# Overview.net
KiCad netlist of a schematic drawn in Altium Designer
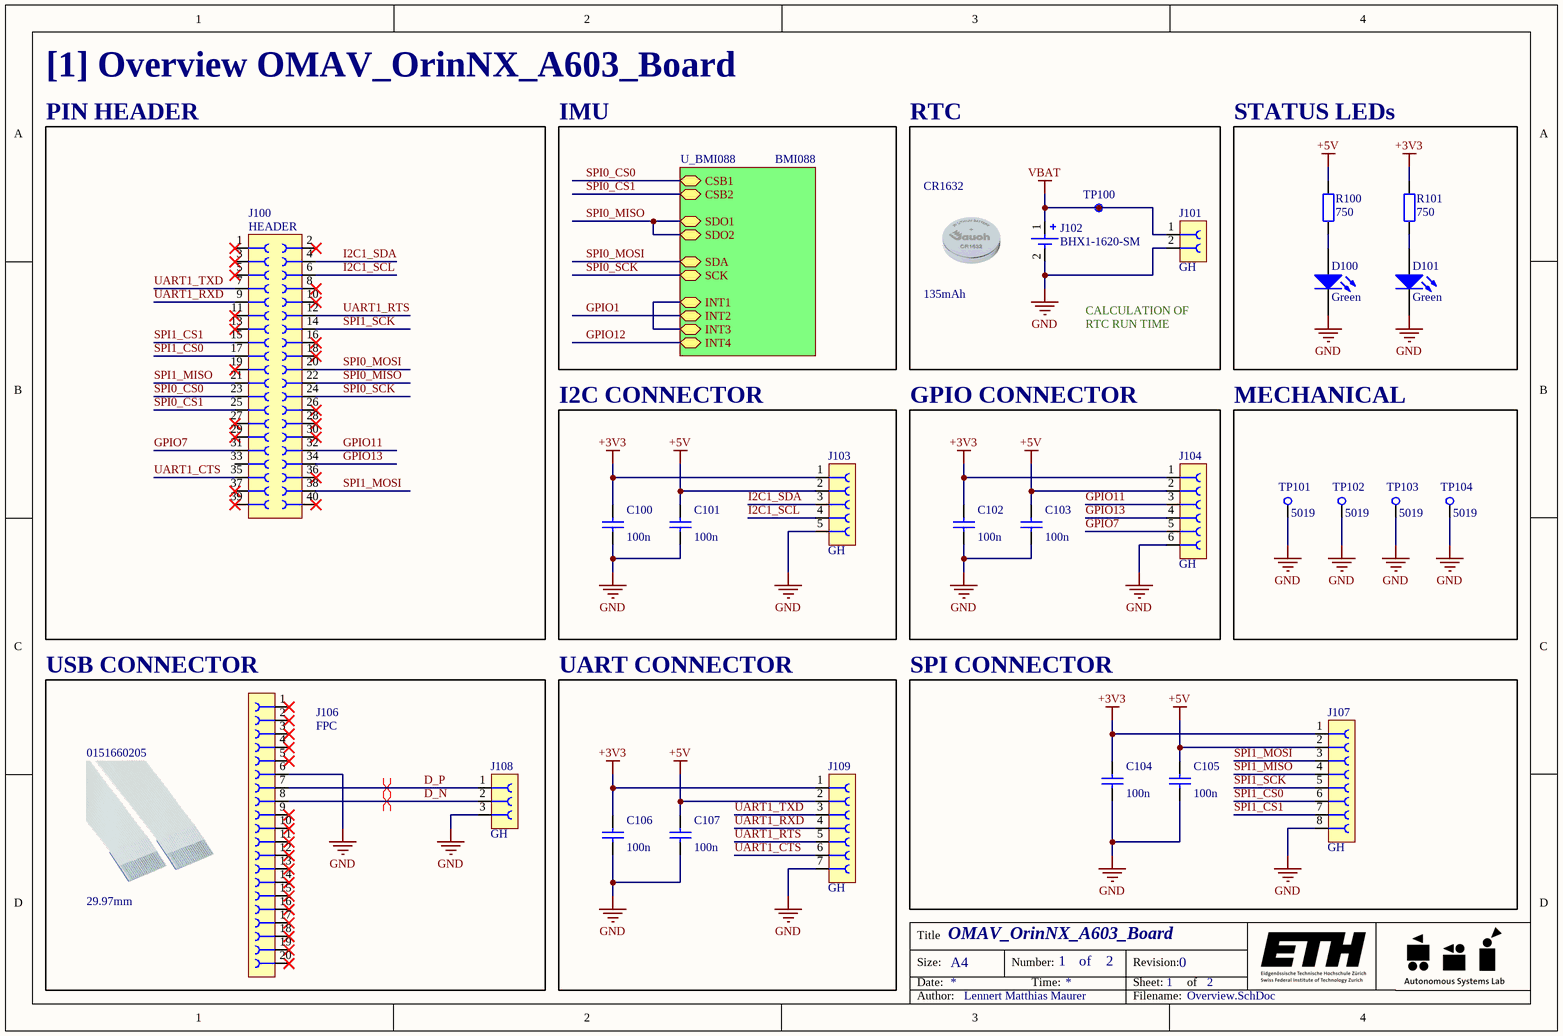
[diagram p0: Overview.SchDoc]

(export (version "E")
  (design (tool "Eeschema 10.0.6"))
  (components
    (comp (ref "C100")
      (value "100n")
      (footprint "SMD_CAPC2012X12N")
      (description "CERCAP 100n 100V 10% X7R 0603")
      (fields
        (field (name "MANUFACTURER") "Murata")
        (field (name "MANUFACTURER PART NUMBER") "GRM188R72A104KA35D")
      )
      (libsource (lib "ETHZ Vault") (part "Cap"))
    )
    (comp (ref "C101")
      (value "100n")
      (footprint "SMD_CAPC2012X12N")
      (description "CERCAP 100n 100V 10% X7R 0603")
      (fields
        (field (name "MANUFACTURER") "Murata")
        (field (name "MANUFACTURER PART NUMBER") "GRM188R72A104KA35D")
      )
      (libsource (lib "ETHZ Vault") (part "Cap"))
    )
    (comp (ref "C102")
      (value "100n")
      (footprint "SMD_CAPC2012X12N")
      (description "CERCAP 100n 100V 10% X7R 0603")
      (fields
        (field (name "MANUFACTURER") "Murata")
        (field (name "MANUFACTURER PART NUMBER") "GRM188R72A104KA35D")
      )
      (libsource (lib "ETHZ Vault") (part "Cap"))
    )
    (comp (ref "C103")
      (value "100n")
      (footprint "SMD_CAPC2012X12N")
      (description "CERCAP 100n 100V 10% X7R 0603")
      (fields
        (field (name "MANUFACTURER") "Murata")
        (field (name "MANUFACTURER PART NUMBER") "GRM188R72A104KA35D")
      )
      (libsource (lib "ETHZ Vault") (part "Cap"))
    )
    (comp (ref "C104")
      (value "100n")
      (footprint "SMD_CAPC2012X12N")
      (description "CERCAP 100n 100V 10% X7R 0603")
      (fields
        (field (name "MANUFACTURER") "Murata")
        (field (name "MANUFACTURER PART NUMBER") "GRM188R72A104KA35D")
      )
      (libsource (lib "ETHZ Vault") (part "Cap"))
    )
    (comp (ref "C105")
      (value "100n")
      (footprint "SMD_CAPC2012X12N")
      (description "CERCAP 100n 100V 10% X7R 0603")
      (fields
        (field (name "MANUFACTURER") "Murata")
        (field (name "MANUFACTURER PART NUMBER") "GRM188R72A104KA35D")
      )
      (libsource (lib "ETHZ Vault") (part "Cap"))
    )
    (comp (ref "C106")
      (value "100n")
      (footprint "SMD_CAPC2012X12N")
      (description "CERCAP 100n 100V 10% X7R 0603")
      (fields
        (field (name "MANUFACTURER") "Murata")
        (field (name "MANUFACTURER PART NUMBER") "GRM188R72A104KA35D")
      )
      (libsource (lib "ETHZ Vault") (part "Cap"))
    )
    (comp (ref "C107")
      (value "100n")
      (footprint "SMD_CAPC2012X12N")
      (description "CERCAP 100n 100V 10% X7R 0603")
      (fields
        (field (name "MANUFACTURER") "Murata")
        (field (name "MANUFACTURER PART NUMBER") "GRM188R72A104KA35D")
      )
      (libsource (lib "ETHZ Vault") (part "Cap"))
    )
    (comp (ref "D100")
      (value "Green")
      (footprint "SMD_LED_0402")
      (description "LED GREEN 2mA  1.9V 1x 0.5mm")
      (fields
        (field (name "MANUFACTURER") "Kingbright USA")
        (field (name "MANUFACTURER PART NUMBER") "APHHS1005LCGCK")
      )
      (libsource (lib "ETHZ Vault") (part "Diode LED"))
    )
    (comp (ref "D101")
      (value "Green")
      (footprint "SMD_LED_0402")
      (description "LED GREEN 2mA  1.9V 1x 0.5mm")
      (fields
        (field (name "MANUFACTURER") "Kingbright USA")
        (field (name "MANUFACTURER PART NUMBER") "APHHS1005LCGCK")
      )
      (libsource (lib "ETHZ Vault") (part "Diode LED"))
    )
    (comp (ref "J100")
      (value "HEADER")
      (footprint "NPTC202KFMS-RC")
      (description "RECT-CONN Female 40-Poles 2.54mm Vertical SMD 12.55x51.3mm")
      (fields
        (field (name "MANUFACTURER") "Sullins Connector Solutions")
        (field (name "MANUFACTURER PART NUMBER") "NPTC202KFMS-RC")
      )
      (libsource (lib "ETHZ Vault") (part "CON 20x2 Female"))
    )
    (comp (ref "J101")
      (value "GH")
      (footprint "SMD_CONN_JST_GH_FEMALE _2-POLES_1.25mm_VERTICAL")
      (description "CONN Female GH 2-Poles 1.25mm Vertical SMD 5.75x4.05mm")
      (fields
        (field (name "MANUFACTURER") "JST Sales America Inc.")
        (field (name "MANUFACTURER PART NUMBER") "BM02B-GHS-TBT(LF)(SN)(N)")
      )
      (libsource (lib "ETHZ Vault") (part "CON 2x1 Female"))
    )
    (comp (ref "J102")
      (value "BHX1-1620-SM")
      (footprint "BHX1-1620-SM")
      (description "EMECH SINGLE COIN BATTERY RETAINER SMD 16x3.55mm")
      (fields (field (name "MANUFACTURER") "MPD (Memory Protection Devices)"))
      (libsource (lib "ETHZ Vault") (part "Battery Holder"))
    )
    (comp (ref "J103")
      (value "GH")
      (footprint "SMD_CONN_JST_GH_FEMALE _5-POLES_1.25mm_VERTICAL")
      (description "CONN Female GH 5-Poles 1.25mm Vertical SMD 9.50x4.05mm")
      (fields
        (field (name "MANUFACTURER") "JST Sales America Inc.")
        (field (name "MANUFACTURER PART NUMBER") "BM05B-GHS-TBT(LF)(SN)(N)")
      )
      (libsource (lib "ETHZ Vault") (part "CON 5x1 Female"))
    )
    (comp (ref "J104")
      (value "GH")
      (footprint "SMD_CONN_JST_GH_FEMALE _6-POLES_1.25mm_VERTICAL")
      (description "CONN Female GH 6-Poles 1.25mm Vertical SMD 10.75x4.05mm")
      (fields
        (field (name "MANUFACTURER") "JST Sales America Inc.")
        (field (name "MANUFACTURER PART NUMBER") "BM06B-GHS-TBT(LF)(SN)(N)")
      )
      (libsource (lib "ETHZ Vault") (part "CON 6x1 Female"))
    )
    (comp (ref "J106")
      (value "FPC")
      (footprint "5034802000")
      (description "FPC TOP/BOTTOM 20POS 0.5mm Horizontal SMD")
      (fields (field (name "MANUFACTURER") "Molex") (field (name "MANUFACTURER PART NUMBER") "5034802000"))
      (libsource (lib "ETHZ Vault") (part "CON 20x1 Female"))
    )
    (comp (ref "J107")
      (value "GH")
      (footprint "SMD_CONN_JST_GH_FEMALE _8-POLES_1.25mm_VERTICAL")
      (description "CONN Female GH 8-Poles 1.25mm Vertical SMD 13.25x4.05mm")
      (fields
        (field (name "MANUFACTURER") "JST Sales America Inc.")
        (field (name "MANUFACTURER PART NUMBER") "455-1584-1-ND")
      )
      (libsource (lib "ETHZ Vault") (part "CON 8x1 Female"))
    )
    (comp (ref "J108")
      (value "GH")
      (footprint "SMD_CONN_JST_GH_FEMALE _3-POLES_1.25mm_VERTICAL")
      (description "CONN Female GH 3-Poles 1.25mm Vertical SMD 7.00x4.05mm")
      (fields
        (field (name "MANUFACTURER") "JST Sales America Inc.")
        (field (name "MANUFACTURER PART NUMBER") "SM03B-GHS-TB(LF)(SN)")
      )
      (libsource (lib "ETHZ Vault") (part "CON 3x1 Female"))
    )
    (comp (ref "J109")
      (value "GH")
      (footprint "SMD_CONN_JST_GH_FEMALE _7-POLES_1.25mm_VERTICAL")
      (description "CONN Female GH 7-Poles 1.25mm Vertical SMD 12.00x4.05mm")
      (fields
        (field (name "MANUFACTURER") "JST Sales America Inc.")
        (field (name "MANUFACTURER PART NUMBER") "BM07B-GHS-TBT(LF)(SN)(N)")
      )
      (libsource (lib "ETHZ Vault") (part "CON 7x1 Female"))
    )
    (comp (ref "MEC100")
      (value "CR1632")
      (description "EMECH SINGLE 3V LITHIUM BATTERY 16mm")
      (fields (field (name "MANUFACTURER") "Jauch Quartz") (field (name "ALTIUM_VALUE") "135mAh"))
      (libsource (lib "ETHZ Vault") (part "CR1632"))
    )
    (comp (ref "MEC101")
      (value "0151660205")
      (description "EMECH SINGLE FFC CABLE 20-Pin 0.5mm 29.97mm")
      (fields (field (name "MANUFACTURER") "Molex") (field (name "ALTIUM_VALUE") "29.97mm"))
      (libsource (lib "ETHZ Vault") (part "0151660205"))
    )
    (comp (ref "R100")
      (value "750")
      (footprint "SMD_RESC1005X04N")
      (description "RES 750 100mW 1% 0402")
      (fields
        (field (name "MANUFACTURER") "Panasonic Electronic Components")
        (field (name "MANUFACTURER PART NUMBER") "ERJ-2RKF7500X")
      )
      (libsource (lib "ETHZ Vault") (part "Res"))
    )
    (comp (ref "R101")
      (value "750")
      (footprint "SMD_RESC1005X04N")
      (description "RES 750 100mW 1% 0402")
      (fields
        (field (name "MANUFACTURER") "Panasonic Electronic Components")
        (field (name "MANUFACTURER PART NUMBER") "ERJ-2RKF7500X")
      )
      (libsource (lib "ETHZ Vault") (part "Res"))
    )
    (comp (ref "TP100")
      (value "Test Point Small")
      (footprint "SMD_PAD_0.5mm")
      (description "TP TESTPOINT MULTIPLE_SIZE")
      (libsource (lib "ETHZ Vault") (part "Test Point Small"))
    )
    (comp (ref "TP101")
      (value "5019")
      (footprint "KEYSTONE_5019")
      (description "TP SMD 3.81x 2.03mm")
      (fields (field (name "MANUFACTURER") "Keystone Electronics"))
      (libsource (lib "ETHZ Vault") (part "Test Point"))
    )
    (comp (ref "TP102")
      (value "5019")
      (footprint "KEYSTONE_5019")
      (description "TP SMD 3.81x 2.03mm")
      (fields (field (name "MANUFACTURER") "Keystone Electronics"))
      (libsource (lib "ETHZ Vault") (part "Test Point"))
    )
    (comp (ref "TP103")
      (value "5019")
      (footprint "KEYSTONE_5019")
      (description "TP SMD 3.81x 2.03mm")
      (fields (field (name "MANUFACTURER") "Keystone Electronics"))
      (libsource (lib "ETHZ Vault") (part "Test Point"))
    )
    (comp (ref "TP104")
      (value "5019")
      (footprint "KEYSTONE_5019")
      (description "TP SMD 3.81x 2.03mm")
      (fields (field (name "MANUFACTURER") "Keystone Electronics"))
      (libsource (lib "ETHZ Vault") (part "Test Point"))
    )
  )
  (nets
    (net (code "1") (name "+3V3") (class "Default")
      (node (ref "C100") (pin "2") (pinfunction "2_2") (pintype "passive"))
      (node (ref "C102") (pin "2") (pinfunction "2_2") (pintype "passive"))
      (node (ref "C104") (pin "2") (pinfunction "2_2") (pintype "passive"))
      (node (ref "C106") (pin "2") (pinfunction "2_2") (pintype "passive"))
      (node (ref "J103") (pin "1") (pinfunction "1_1") (pintype "passive"))
      (node (ref "J104") (pin "1") (pinfunction "1_1") (pintype "passive"))
      (node (ref "J107") (pin "1") (pinfunction "1_1") (pintype "passive"))
      (node (ref "J109") (pin "1") (pinfunction "1_1") (pintype "passive"))
      (node (ref "R101") (pin "2") (pinfunction "2_2") (pintype "passive"))
    )
    (net (code "2") (name "+5V") (class "Default")
      (node (ref "C101") (pin "2") (pinfunction "2_2") (pintype "passive"))
      (node (ref "C103") (pin "2") (pinfunction "2_2") (pintype "passive"))
      (node (ref "C105") (pin "2") (pinfunction "2_2") (pintype "passive"))
      (node (ref "C107") (pin "2") (pinfunction "2_2") (pintype "passive"))
      (node (ref "J103") (pin "2") (pinfunction "2_2") (pintype "passive"))
      (node (ref "J104") (pin "2") (pinfunction "2_2") (pintype "passive"))
      (node (ref "J107") (pin "2") (pinfunction "2_2") (pintype "passive"))
      (node (ref "J109") (pin "2") (pinfunction "2_2") (pintype "passive"))
      (node (ref "R100") (pin "2") (pinfunction "2_2") (pintype "passive"))
    )
    (net (code "3") (name "/D_N") (class "Default")
      (node (ref "J106") (pin "8") (pinfunction "8_8") (pintype "passive"))
      (node (ref "J108") (pin "2") (pinfunction "2_2") (pintype "passive"))
    )
    (net (code "4") (name "/D_P") (class "Default")
      (node (ref "J106") (pin "7") (pinfunction "7_7") (pintype "passive"))
      (node (ref "J108") (pin "1") (pinfunction "1_1") (pintype "passive"))
    )
    (net (code "6") (name "/GPIO7") (class "Default")
      (node (ref "J100") (pin "31") (pinfunction "31_31") (pintype "passive"))
      (node (ref "J104") (pin "5") (pinfunction "5_5") (pintype "passive"))
    )
    (net (code "7") (name "/GPIO11") (class "Default")
      (node (ref "J100") (pin "32") (pinfunction "32_32") (pintype "passive"))
      (node (ref "J104") (pin "3") (pinfunction "3_3") (pintype "passive"))
    )
    (net (code "9") (name "/GPIO13") (class "Default")
      (node (ref "J100") (pin "34") (pinfunction "34_34") (pintype "passive"))
      (node (ref "J104") (pin "4") (pinfunction "4_4") (pintype "passive"))
    )
    (net (code "10") (name "/I2C1_SCL") (class "Default")
      (node (ref "J100") (pin "6") (pinfunction "6_6") (pintype "passive"))
      (node (ref "J103") (pin "4") (pinfunction "4_4") (pintype "passive"))
    )
    (net (code "11") (name "/I2C1_SDA") (class "Default")
      (node (ref "J100") (pin "4") (pinfunction "4_4") (pintype "passive"))
      (node (ref "J103") (pin "3") (pinfunction "3_3") (pintype "passive"))
    )
    (net (code "13") (name "/SPI0_CS0") (class "Default")
      (node (ref "J100") (pin "23") (pinfunction "23_23") (pintype "passive"))
    )
    (net (code "14") (name "/SPI0_CS1") (class "Default")
      (node (ref "J100") (pin "25") (pinfunction "25_25") (pintype "passive"))
    )
    (net (code "15") (name "/SPI0_MISO") (class "Default")
      (node (ref "J100") (pin "22") (pinfunction "22_22") (pintype "passive"))
    )
    (net (code "16") (name "/SPI0_MOSI") (class "Default")
      (node (ref "J100") (pin "20") (pinfunction "20_20") (pintype "passive"))
    )
    (net (code "17") (name "/SPI0_SCK") (class "Default")
      (node (ref "J100") (pin "24") (pinfunction "24_24") (pintype "passive"))
    )
    (net (code "18") (name "/SPI1_CS0") (class "Default")
      (node (ref "J100") (pin "17") (pinfunction "17_17") (pintype "passive"))
      (node (ref "J107") (pin "6") (pinfunction "6_6") (pintype "passive"))
    )
    (net (code "19") (name "/SPI1_CS1") (class "Default")
      (node (ref "J100") (pin "15") (pinfunction "15_15") (pintype "passive"))
      (node (ref "J107") (pin "7") (pinfunction "7_7") (pintype "passive"))
    )
    (net (code "20") (name "/SPI1_MISO") (class "Default")
      (node (ref "J100") (pin "21") (pinfunction "21_21") (pintype "passive"))
      (node (ref "J107") (pin "4") (pinfunction "4_4") (pintype "passive"))
    )
    (net (code "21") (name "/SPI1_MOSI") (class "Default")
      (node (ref "J100") (pin "38") (pinfunction "38_38") (pintype "passive"))
      (node (ref "J107") (pin "3") (pinfunction "3_3") (pintype "passive"))
    )
    (net (code "22") (name "/SPI1_SCK") (class "Default")
      (node (ref "J100") (pin "14") (pinfunction "14_14") (pintype "passive"))
      (node (ref "J107") (pin "5") (pinfunction "5_5") (pintype "passive"))
    )
    (net (code "23") (name "/UART1_CTS") (class "Default")
      (node (ref "J100") (pin "35") (pinfunction "35_35") (pintype "passive"))
      (node (ref "J109") (pin "6") (pinfunction "6_6") (pintype "passive"))
    )
    (net (code "24") (name "/UART1_RTS") (class "Default")
      (node (ref "J100") (pin "12") (pinfunction "12_12") (pintype "passive"))
      (node (ref "J109") (pin "5") (pinfunction "5_5") (pintype "passive"))
    )
    (net (code "25") (name "/UART1_RXD") (class "Default")
      (node (ref "J100") (pin "9") (pinfunction "9_9") (pintype "passive"))
      (node (ref "J109") (pin "4") (pinfunction "4_4") (pintype "passive"))
    )
    (net (code "26") (name "/UART1_TXD") (class "Default")
      (node (ref "J100") (pin "7") (pinfunction "7_7") (pintype "passive"))
      (node (ref "J109") (pin "3") (pinfunction "3_3") (pintype "passive"))
    )
    (net (code "27") (name "GND") (class "Default")
      (node (ref "C100") (pin "1") (pinfunction "1_1") (pintype "passive"))
      (node (ref "C101") (pin "1") (pinfunction "1_1") (pintype "passive"))
      (node (ref "C102") (pin "1") (pinfunction "1_1") (pintype "passive"))
      (node (ref "C103") (pin "1") (pinfunction "1_1") (pintype "passive"))
      (node (ref "C104") (pin "1") (pinfunction "1_1") (pintype "passive"))
      (node (ref "C105") (pin "1") (pinfunction "1_1") (pintype "passive"))
      (node (ref "C106") (pin "1") (pinfunction "1_1") (pintype "passive"))
      (node (ref "C107") (pin "1") (pinfunction "1_1") (pintype "passive"))
      (node (ref "D100") (pin "1") (pinfunction "K_1") (pintype "passive"))
      (node (ref "D101") (pin "1") (pinfunction "K_1") (pintype "passive"))
      (node (ref "J101") (pin "2") (pinfunction "2_2") (pintype "passive"))
      (node (ref "J102") (pin "2") (pinfunction "-_2") (pintype "passive"))
      (node (ref "J103") (pin "5") (pinfunction "5_5") (pintype "passive"))
      (node (ref "J104") (pin "6") (pinfunction "6_6") (pintype "passive"))
      (node (ref "J106") (pin "6") (pinfunction "6_6") (pintype "passive"))
      (node (ref "J107") (pin "8") (pinfunction "8_8") (pintype "passive"))
      (node (ref "J108") (pin "3") (pinfunction "3_3") (pintype "passive"))
      (node (ref "J109") (pin "7") (pinfunction "7_7") (pintype "passive"))
      (node (ref "TP101") (pin "1") (pinfunction "1_1") (pintype "passive"))
      (node (ref "TP102") (pin "1") (pinfunction "1_1") (pintype "passive"))
      (node (ref "TP103") (pin "1") (pinfunction "1_1") (pintype "passive"))
      (node (ref "TP104") (pin "1") (pinfunction "1_1") (pintype "passive"))
    )
    (net (code "28") (name "Net-(D100-A)") (class "Default")
      (node (ref "D100") (pin "2") (pinfunction "A_2") (pintype "passive"))
      (node (ref "R100") (pin "1") (pinfunction "1_1") (pintype "passive"))
    )
    (net (code "29") (name "Net-(D101-A)") (class "Default")
      (node (ref "D101") (pin "2") (pinfunction "A_2") (pintype "passive"))
      (node (ref "R101") (pin "1") (pinfunction "1_1") (pintype "passive"))
    )
    (net (code "30") (name "VBAT") (class "Default")
      (node (ref "J101") (pin "1") (pinfunction "1_1") (pintype "passive"))
      (node (ref "J102") (pin "1") (pinfunction "+_1") (pintype "passive"))
      (node (ref "TP100") (pin "1") (pinfunction "1_1") (pintype "passive"))
    )
    (net (code "31") (name "unconnected-(J100-Pad1)") (class "Default")
      (node (ref "J100") (pin "1") (pinfunction "1_1") (pintype "passive+no_connect"))
    )
    (net (code "32") (name "unconnected-(J100-Pad2)") (class "Default")
      (node (ref "J100") (pin "2") (pinfunction "2_2") (pintype "passive+no_connect"))
    )
    (net (code "33") (name "unconnected-(J100-Pad3)") (class "Default")
      (node (ref "J100") (pin "3") (pinfunction "3_3") (pintype "passive+no_connect"))
    )
    (net (code "34") (name "unconnected-(J100-Pad5)") (class "Default")
      (node (ref "J100") (pin "5") (pinfunction "5_5") (pintype "passive+no_connect"))
    )
    (net (code "35") (name "unconnected-(J100-Pad8)") (class "Default")
      (node (ref "J100") (pin "8") (pinfunction "8_8") (pintype "passive+no_connect"))
    )
    (net (code "36") (name "unconnected-(J100-Pad10)") (class "Default")
      (node (ref "J100") (pin "10") (pinfunction "10_10") (pintype "passive+no_connect"))
    )
    (net (code "37") (name "unconnected-(J100-Pad11)") (class "Default")
      (node (ref "J100") (pin "11") (pinfunction "11_11") (pintype "passive+no_connect"))
    )
    (net (code "38") (name "unconnected-(J100-Pad13)") (class "Default")
      (node (ref "J100") (pin "13") (pinfunction "13_13") (pintype "passive+no_connect"))
    )
    (net (code "39") (name "unconnected-(J100-Pad16)") (class "Default")
      (node (ref "J100") (pin "16") (pinfunction "16_16") (pintype "passive+no_connect"))
    )
    (net (code "40") (name "unconnected-(J100-Pad18)") (class "Default")
      (node (ref "J100") (pin "18") (pinfunction "18_18") (pintype "passive+no_connect"))
    )
    (net (code "41") (name "unconnected-(J100-Pad19)") (class "Default")
      (node (ref "J100") (pin "19") (pinfunction "19_19") (pintype "passive+no_connect"))
    )
    (net (code "42") (name "unconnected-(J100-Pad26)") (class "Default")
      (node (ref "J100") (pin "26") (pinfunction "26_26") (pintype "passive+no_connect"))
    )
    (net (code "43") (name "unconnected-(J100-Pad27)") (class "Default")
      (node (ref "J100") (pin "27") (pinfunction "27_27") (pintype "passive+no_connect"))
    )
    (net (code "44") (name "unconnected-(J100-Pad28)") (class "Default")
      (node (ref "J100") (pin "28") (pinfunction "28_28") (pintype "passive+no_connect"))
    )
    (net (code "45") (name "unconnected-(J100-Pad29)") (class "Default")
      (node (ref "J100") (pin "29") (pinfunction "29_29") (pintype "passive+no_connect"))
    )
    (net (code "46") (name "unconnected-(J100-Pad30)") (class "Default")
      (node (ref "J100") (pin "30") (pinfunction "30_30") (pintype "passive+no_connect"))
    )
    (net (code "47") (name "unconnected-(J100-Pad33)") (class "Default")
      (node (ref "J100") (pin "33") (pinfunction "33_33") (pintype "passive"))
    )
    (net (code "48") (name "unconnected-(J100-Pad36)") (class "Default")
      (node (ref "J100") (pin "36") (pinfunction "36_36") (pintype "passive+no_connect"))
    )
    (net (code "49") (name "unconnected-(J100-Pad37)") (class "Default")
      (node (ref "J100") (pin "37") (pinfunction "37_37") (pintype "passive+no_connect"))
    )
    (net (code "50") (name "unconnected-(J100-Pad39)") (class "Default")
      (node (ref "J100") (pin "39") (pinfunction "39_39") (pintype "passive+no_connect"))
    )
    (net (code "51") (name "unconnected-(J100-Pad40)") (class "Default")
      (node (ref "J100") (pin "40") (pinfunction "40_40") (pintype "passive+no_connect"))
    )
    (net (code "52") (name "unconnected-(J106-Pad1)") (class "Default")
      (node (ref "J106") (pin "1") (pinfunction "1_1") (pintype "passive+no_connect"))
    )
    (net (code "53") (name "unconnected-(J106-Pad2)") (class "Default")
      (node (ref "J106") (pin "2") (pinfunction "2_2") (pintype "passive+no_connect"))
    )
    (net (code "54") (name "unconnected-(J106-Pad3)") (class "Default")
      (node (ref "J106") (pin "3") (pinfunction "3_3") (pintype "passive+no_connect"))
    )
    (net (code "55") (name "unconnected-(J106-Pad4)") (class "Default")
      (node (ref "J106") (pin "4") (pinfunction "4_4") (pintype "passive+no_connect"))
    )
    (net (code "56") (name "unconnected-(J106-Pad5)") (class "Default")
      (node (ref "J106") (pin "5") (pinfunction "5_5") (pintype "passive+no_connect"))
    )
    (net (code "57") (name "unconnected-(J106-Pad9)") (class "Default")
      (node (ref "J106") (pin "9") (pinfunction "9_9") (pintype "passive+no_connect"))
    )
    (net (code "58") (name "unconnected-(J106-Pad10)") (class "Default")
      (node (ref "J106") (pin "10") (pinfunction "10_10") (pintype "passive+no_connect"))
    )
    (net (code "59") (name "unconnected-(J106-Pad11)") (class "Default")
      (node (ref "J106") (pin "11") (pinfunction "11_11") (pintype "passive+no_connect"))
    )
    (net (code "60") (name "unconnected-(J106-Pad12)") (class "Default")
      (node (ref "J106") (pin "12") (pinfunction "12_12") (pintype "passive+no_connect"))
    )
    (net (code "61") (name "unconnected-(J106-Pad13)") (class "Default")
      (node (ref "J106") (pin "13") (pinfunction "13_13") (pintype "passive+no_connect"))
    )
    (net (code "62") (name "unconnected-(J106-Pad14)") (class "Default")
      (node (ref "J106") (pin "14") (pinfunction "14_14") (pintype "passive+no_connect"))
    )
    (net (code "63") (name "unconnected-(J106-Pad15)") (class "Default")
      (node (ref "J106") (pin "15") (pinfunction "15_15") (pintype "passive+no_connect"))
    )
    (net (code "64") (name "unconnected-(J106-Pad16)") (class "Default")
      (node (ref "J106") (pin "16") (pinfunction "16_16") (pintype "passive+no_connect"))
    )
    (net (code "65") (name "unconnected-(J106-Pad17)") (class "Default")
      (node (ref "J106") (pin "17") (pinfunction "17_17") (pintype "passive+no_connect"))
    )
    (net (code "66") (name "unconnected-(J106-Pad18)") (class "Default")
      (node (ref "J106") (pin "18") (pinfunction "18_18") (pintype "passive+no_connect"))
    )
    (net (code "67") (name "unconnected-(J106-Pad19)") (class "Default")
      (node (ref "J106") (pin "19") (pinfunction "19_19") (pintype "passive+no_connect"))
    )
    (net (code "68") (name "unconnected-(J106-Pad20)") (class "Default")
      (node (ref "J106") (pin "20") (pinfunction "20_20") (pintype "passive+no_connect"))
    )
  )
)
